# ou6_cs-base_V1_0.net
KiCad netlist of a schematic drawn in EAGLE
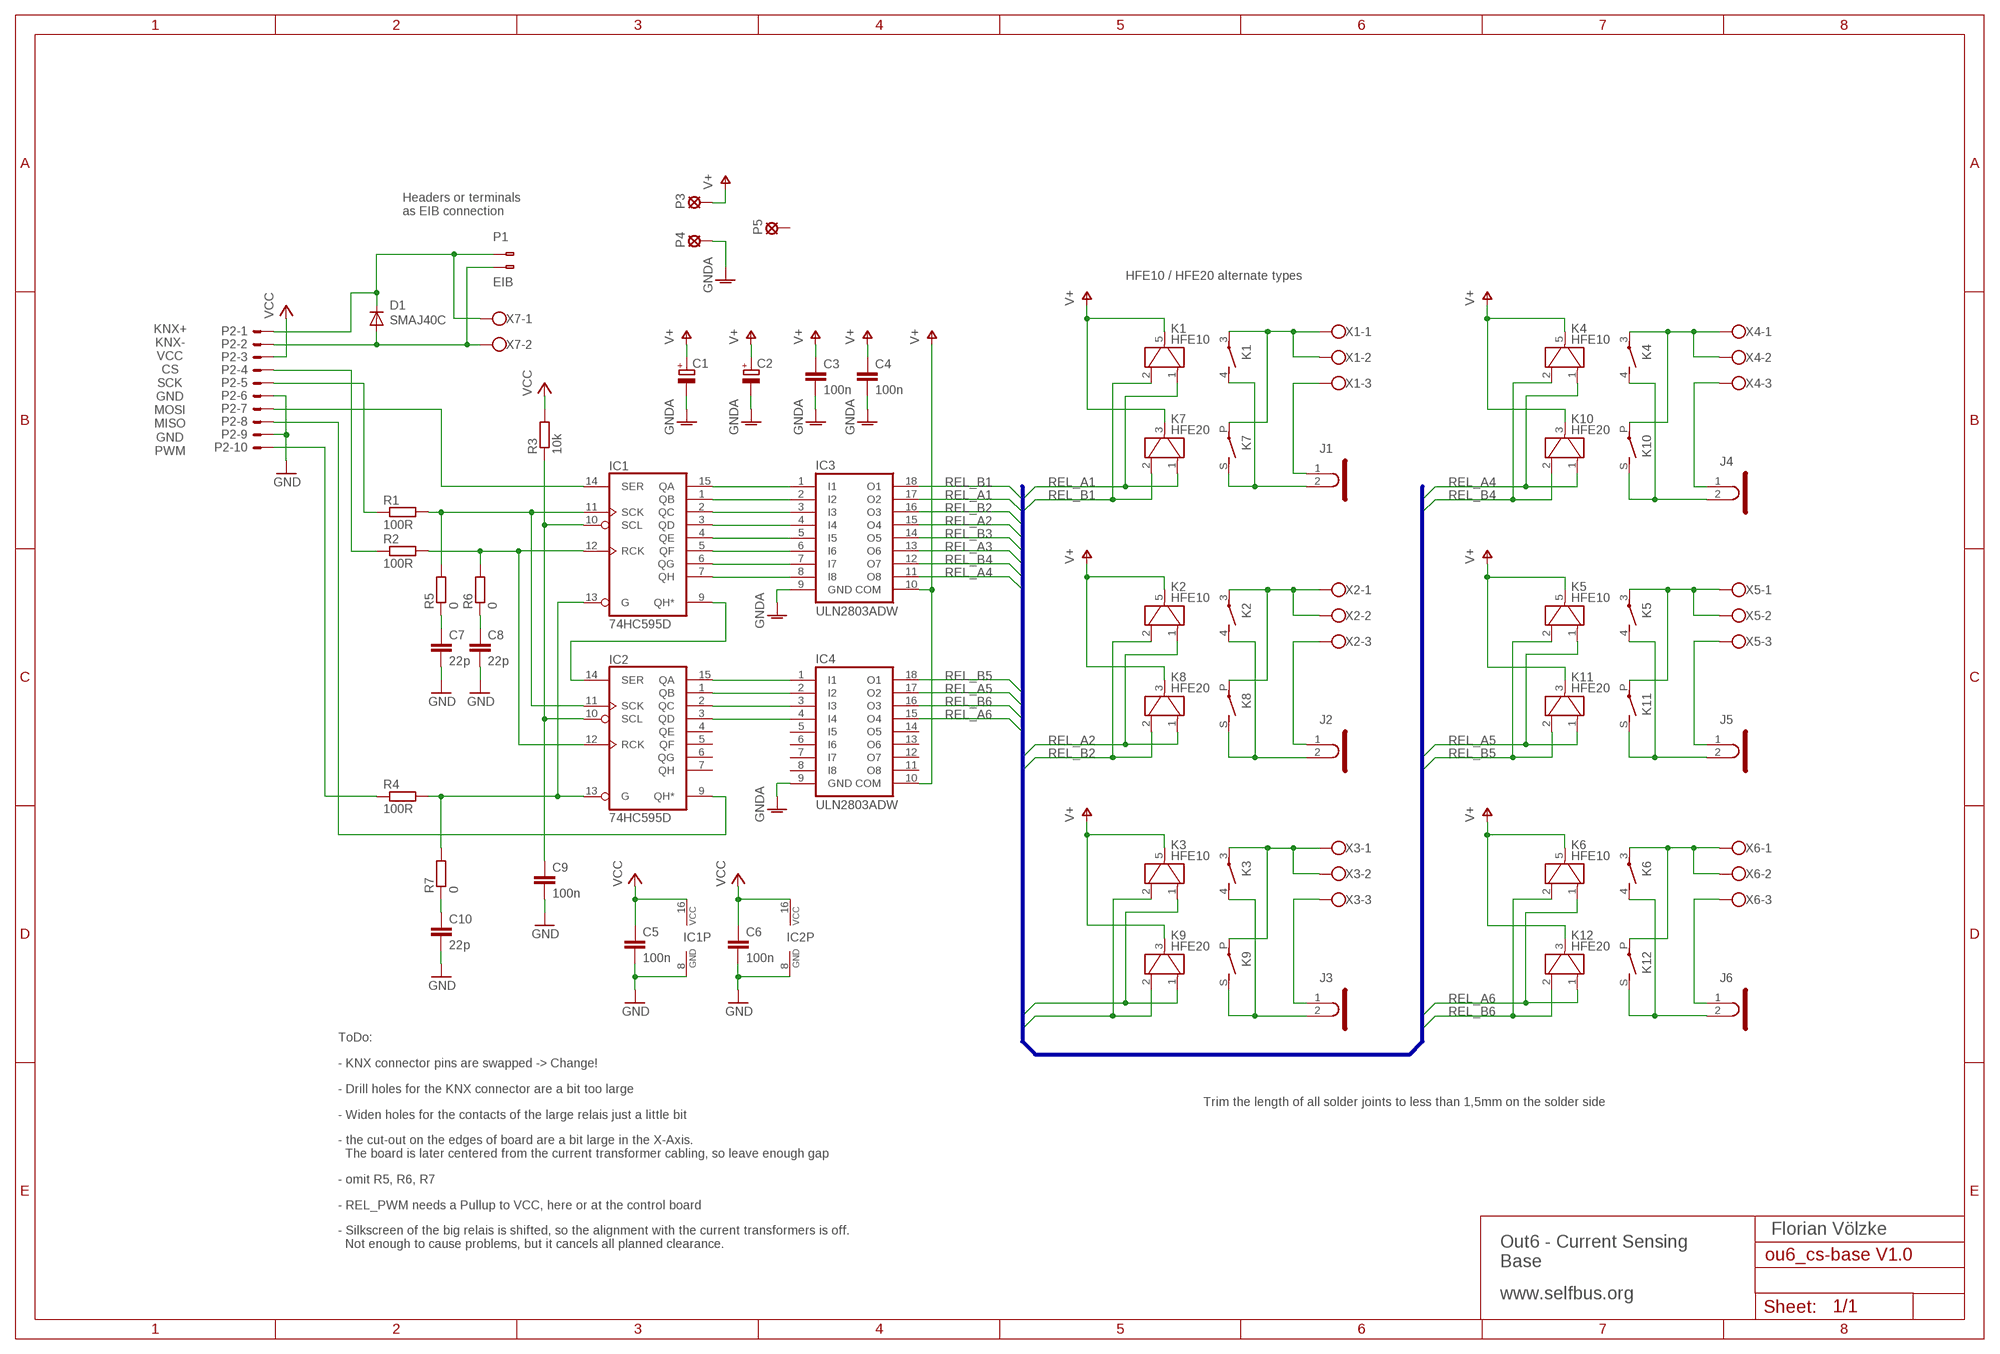
[diagram p0: schematic, sheet 1]

(export (version "E")
  (design (tool "Eeschema 10.0.6"))
  (components
    (comp (ref "C1")
      (value "CPOL-EUE5-13-20")
      (footprint "eagle-import:E5-13-20")
      (libsource (lib "eagle-import") (part "CPOL-EUE5-13-20"))
    )
    (comp (ref "C2")
      (value "CPOL-EUE5-13-20R")
      (footprint "eagle-import:E5-13-20R")
      (libsource (lib "eagle-import") (part "CPOL-EUE5-13-20R"))
    )
    (comp (ref "C3")
      (value "100n")
      (footprint "eagle-import:R0805M")
      (libsource (lib "eagle-import") (part "C-EUC0805M"))
    )
    (comp (ref "C4")
      (value "100n")
      (footprint "eagle-import:R0805M")
      (libsource (lib "eagle-import") (part "C-EUC0805M"))
    )
    (comp (ref "C5")
      (value "100n")
      (footprint "eagle-import:R0805M")
      (libsource (lib "eagle-import") (part "C-EUC0805M"))
    )
    (comp (ref "C6")
      (value "100n")
      (footprint "eagle-import:R0805M")
      (libsource (lib "eagle-import") (part "C-EUC0805M"))
    )
    (comp (ref "C7")
      (value "22p")
      (footprint "eagle-import:R0805M")
      (libsource (lib "eagle-import") (part "C-EUC0805M"))
    )
    (comp (ref "C8")
      (value "22p")
      (footprint "eagle-import:R0805M")
      (libsource (lib "eagle-import") (part "C-EUC0805M"))
    )
    (comp (ref "C9")
      (value "100n")
      (footprint "eagle-import:R0805M")
      (libsource (lib "eagle-import") (part "C-EUC0805M"))
    )
    (comp (ref "C10")
      (value "22p")
      (footprint "eagle-import:R0805M")
      (libsource (lib "eagle-import") (part "C-EUC0805M"))
    )
    (comp (ref "D1")
      (value "SMAJ40C")
      (footprint "eagle-import:SMB")
      (libsource (lib "eagle-import") (part "D-SMB"))
    )
    (comp (ref "IC1")
      (value "74HC595D")
      (footprint "eagle-import:SO16")
      (libsource (lib "eagle-import") (part "74595DHC"))
    )
    (comp (ref "IC2")
      (value "74HC595D")
      (footprint "eagle-import:SO16")
      (libsource (lib "eagle-import") (part "74595DHC"))
    )
    (comp (ref "IC3")
      (value "ULN2803ADW")
      (footprint "eagle-import:SO18W")
      (libsource (lib "eagle-import") (part "ULN2803ADW"))
    )
    (comp (ref "IC4")
      (value "ULN2803ADW")
      (footprint "eagle-import:SO18W")
      (libsource (lib "eagle-import") (part "ULN2803ADW"))
    )
    (comp (ref "J1")
      (value "IXFORMER_PRIMONLY")
      (footprint "eagle-import:IXFORMERANTIPART")
      (libsource (lib "eagle-import") (part "IXFORMER_PRIMONLY"))
    )
    (comp (ref "J2")
      (value "IXFORMER_PRIMONLY")
      (footprint "eagle-import:IXFORMERANTIPART")
      (libsource (lib "eagle-import") (part "IXFORMER_PRIMONLY"))
    )
    (comp (ref "J3")
      (value "IXFORMER_PRIMONLY")
      (footprint "eagle-import:IXFORMERANTIPART")
      (libsource (lib "eagle-import") (part "IXFORMER_PRIMONLY"))
    )
    (comp (ref "J4")
      (value "IXFORMER_PRIMONLY")
      (footprint "eagle-import:IXFORMERANTIPART")
      (libsource (lib "eagle-import") (part "IXFORMER_PRIMONLY"))
    )
    (comp (ref "J5")
      (value "IXFORMER_PRIMONLY")
      (footprint "eagle-import:IXFORMERANTIPART")
      (libsource (lib "eagle-import") (part "IXFORMER_PRIMONLY"))
    )
    (comp (ref "J6")
      (value "IXFORMER_PRIMONLY")
      (footprint "eagle-import:IXFORMERANTIPART")
      (libsource (lib "eagle-import") (part "IXFORMER_PRIMONLY"))
    )
    (comp (ref "K1")
      (value "HFE10")
      (footprint "eagle-import:PCB_REL_BIG_POWER_NO")
      (libsource (lib "eagle-import") (part "BISTABLE2C_PCB_SNGLPINHFE10"))
    )
    (comp (ref "K2")
      (value "HFE10")
      (footprint "eagle-import:PCB_REL_BIG_POWER_NO")
      (libsource (lib "eagle-import") (part "BISTABLE2C_PCB_SNGLPINHFE10"))
    )
    (comp (ref "K3")
      (value "HFE10")
      (footprint "eagle-import:PCB_REL_BIG_POWER_NO")
      (libsource (lib "eagle-import") (part "BISTABLE2C_PCB_SNGLPINHFE10"))
    )
    (comp (ref "K4")
      (value "HFE10")
      (footprint "eagle-import:PCB_REL_BIG_POWER_NO")
      (libsource (lib "eagle-import") (part "BISTABLE2C_PCB_SNGLPINHFE10"))
    )
    (comp (ref "K5")
      (value "HFE10")
      (footprint "eagle-import:PCB_REL_BIG_POWER_NO")
      (libsource (lib "eagle-import") (part "BISTABLE2C_PCB_SNGLPINHFE10"))
    )
    (comp (ref "K6")
      (value "HFE10")
      (footprint "eagle-import:PCB_REL_BIG_POWER_NO")
      (libsource (lib "eagle-import") (part "BISTABLE2C_PCB_SNGLPINHFE10"))
    )
    (comp (ref "K7")
      (value "HFE20")
      (footprint "eagle-import:PCB_REL_HP_NO_SNGLPIN")
      (libsource (lib "eagle-import") (part "BISTABLE2C_PCB_SNGLPINHFE20"))
    )
    (comp (ref "K8")
      (value "HFE20")
      (footprint "eagle-import:PCB_REL_HP_NO_SNGLPIN")
      (libsource (lib "eagle-import") (part "BISTABLE2C_PCB_SNGLPINHFE20"))
    )
    (comp (ref "K9")
      (value "HFE20")
      (footprint "eagle-import:PCB_REL_HP_NO_SNGLPIN")
      (libsource (lib "eagle-import") (part "BISTABLE2C_PCB_SNGLPINHFE20"))
    )
    (comp (ref "K10")
      (value "HFE20")
      (footprint "eagle-import:PCB_REL_HP_NO_SNGLPIN")
      (libsource (lib "eagle-import") (part "BISTABLE2C_PCB_SNGLPINHFE20"))
    )
    (comp (ref "K11")
      (value "HFE20")
      (footprint "eagle-import:PCB_REL_HP_NO_SNGLPIN")
      (libsource (lib "eagle-import") (part "BISTABLE2C_PCB_SNGLPINHFE20"))
    )
    (comp (ref "K12")
      (value "HFE20")
      (footprint "eagle-import:PCB_REL_HP_NO_SNGLPIN")
      (libsource (lib "eagle-import") (part "BISTABLE2C_PCB_SNGLPINHFE20"))
    )
    (comp (ref "P1")
      (value "EIB")
      (footprint "eagle-import:BUSKLEMME243-724")
      (libsource (lib "eagle-import") (part "EIB"))
    )
    (comp (ref "P2")
      (value "ML10E")
      (footprint "eagle-import:ML10")
      (libsource (lib "eagle-import") (part "ML10?E"))
    )
    (comp (ref "P3")
      (value "SE1.5")
      (footprint "eagle-import:SE15")
      (libsource (lib "eagle-import") (part "SE1.5"))
    )
    (comp (ref "P4")
      (value "SE1.5")
      (footprint "eagle-import:SE15")
      (libsource (lib "eagle-import") (part "SE1.5"))
    )
    (comp (ref "P5")
      (value "SE1.5")
      (footprint "eagle-import:SE15")
      (libsource (lib "eagle-import") (part "SE1.5"))
    )
    (comp (ref "R1")
      (value "100R")
      (footprint "eagle-import:R0805M")
      (libsource (lib "eagle-import") (part "R-EU_R0805M"))
    )
    (comp (ref "R2")
      (value "100R")
      (footprint "eagle-import:R0805M")
      (libsource (lib "eagle-import") (part "R-EU_R0805M"))
    )
    (comp (ref "R3")
      (value "10k")
      (footprint "eagle-import:R0805M")
      (libsource (lib "eagle-import") (part "R-EU_R0805M"))
    )
    (comp (ref "R4")
      (value "100R")
      (footprint "eagle-import:R0805M")
      (libsource (lib "eagle-import") (part "R-EU_R0805M"))
    )
    (comp (ref "R5")
      (value "0")
      (footprint "eagle-import:R0805M")
      (libsource (lib "eagle-import") (part "R-EU_R0805M"))
    )
    (comp (ref "R6")
      (value "0")
      (footprint "eagle-import:R0805M")
      (libsource (lib "eagle-import") (part "R-EU_R0805M"))
    )
    (comp (ref "R7")
      (value "0")
      (footprint "eagle-import:R0805M")
      (libsource (lib "eagle-import") (part "R-EU_R0805M"))
    )
    (comp (ref "X1")
      (value "KLEMME3POL5_08")
      (footprint "eagle-import:KLEMME3POL5_08")
      (libsource (lib "eagle-import") (part "KLEMME3POL5_08"))
    )
    (comp (ref "X2")
      (value "KLEMME3POL5_08")
      (footprint "eagle-import:KLEMME3POL5_08")
      (libsource (lib "eagle-import") (part "KLEMME3POL5_08"))
    )
    (comp (ref "X3")
      (value "KLEMME3POL5_08")
      (footprint "eagle-import:KLEMME3POL5_08")
      (libsource (lib "eagle-import") (part "KLEMME3POL5_08"))
    )
    (comp (ref "X4")
      (value "KLEMME3POL5_08")
      (footprint "eagle-import:KLEMME3POL5_08")
      (libsource (lib "eagle-import") (part "KLEMME3POL5_08"))
    )
    (comp (ref "X5")
      (value "KLEMME3POL5_08")
      (footprint "eagle-import:KLEMME3POL5_08")
      (libsource (lib "eagle-import") (part "KLEMME3POL5_08"))
    )
    (comp (ref "X6")
      (value "KLEMME3POL5_08")
      (footprint "eagle-import:KLEMME3POL5_08")
      (libsource (lib "eagle-import") (part "KLEMME3POL5_08"))
    )
    (comp (ref "X7")
      (value "KLEMME2POL5_08")
      (footprint "eagle-import:KLEMME2POL5_08")
      (libsource (lib "eagle-import") (part "KLEMME2POL5_08"))
    )
  )
  (nets
    (net (code "1") (name "/REL_A1") (class "Default")
      (node (ref "IC3") (pin "17") (pinfunction "O2_17") (pintype "open_collector"))
      (node (ref "K1") (pin "1") (pinfunction "3_1") (pintype "passive"))
      (node (ref "K7") (pin "1") (pinfunction "3_1") (pintype "passive"))
    )
    (net (code "2") (name "/REL_A2") (class "Default")
      (node (ref "IC3") (pin "15") (pinfunction "O4_15") (pintype "open_collector"))
      (node (ref "K2") (pin "1") (pinfunction "3_1") (pintype "passive"))
      (node (ref "K8") (pin "1") (pinfunction "3_1") (pintype "passive"))
    )
    (net (code "3") (name "/REL_A3") (class "Default")
      (node (ref "IC3") (pin "13") (pinfunction "O6_13") (pintype "open_collector"))
      (node (ref "K3") (pin "1") (pinfunction "3_1") (pintype "passive"))
      (node (ref "K9") (pin "1") (pinfunction "3_1") (pintype "passive"))
    )
    (net (code "4") (name "/REL_A4") (class "Default")
      (node (ref "IC3") (pin "11") (pinfunction "O8_11") (pintype "open_collector"))
      (node (ref "K10") (pin "1") (pinfunction "3_1") (pintype "passive"))
      (node (ref "K4") (pin "1") (pinfunction "3_1") (pintype "passive"))
    )
    (net (code "5") (name "/REL_A5") (class "Default")
      (node (ref "IC4") (pin "17") (pinfunction "O2_17") (pintype "open_collector"))
      (node (ref "K11") (pin "1") (pinfunction "3_1") (pintype "passive"))
      (node (ref "K5") (pin "1") (pinfunction "3_1") (pintype "passive"))
    )
    (net (code "6") (name "/REL_A6") (class "Default")
      (node (ref "IC4") (pin "15") (pinfunction "O4_15") (pintype "open_collector"))
      (node (ref "K12") (pin "1") (pinfunction "3_1") (pintype "passive"))
      (node (ref "K6") (pin "1") (pinfunction "3_1") (pintype "passive"))
    )
    (net (code "7") (name "/REL_B1") (class "Default")
      (node (ref "IC3") (pin "18") (pinfunction "O1_18") (pintype "open_collector"))
      (node (ref "K1") (pin "2") (pinfunction "2_2") (pintype "passive"))
      (node (ref "K7") (pin "2") (pinfunction "2_2") (pintype "passive"))
    )
    (net (code "8") (name "/REL_B2") (class "Default")
      (node (ref "IC3") (pin "16") (pinfunction "O3_16") (pintype "open_collector"))
      (node (ref "K2") (pin "2") (pinfunction "2_2") (pintype "passive"))
      (node (ref "K8") (pin "2") (pinfunction "2_2") (pintype "passive"))
    )
    (net (code "9") (name "/REL_B3") (class "Default")
      (node (ref "IC3") (pin "14") (pinfunction "O5_14") (pintype "open_collector"))
      (node (ref "K3") (pin "2") (pinfunction "2_2") (pintype "passive"))
      (node (ref "K9") (pin "2") (pinfunction "2_2") (pintype "passive"))
    )
    (net (code "10") (name "/REL_B4") (class "Default")
      (node (ref "IC3") (pin "12") (pinfunction "O7_12") (pintype "open_collector"))
      (node (ref "K10") (pin "2") (pinfunction "2_2") (pintype "passive"))
      (node (ref "K4") (pin "2") (pinfunction "2_2") (pintype "passive"))
    )
    (net (code "11") (name "/REL_B5") (class "Default")
      (node (ref "IC4") (pin "18") (pinfunction "O1_18") (pintype "open_collector"))
      (node (ref "K11") (pin "2") (pinfunction "2_2") (pintype "passive"))
      (node (ref "K5") (pin "2") (pinfunction "2_2") (pintype "passive"))
    )
    (net (code "12") (name "/REL_B6") (class "Default")
      (node (ref "IC4") (pin "16") (pinfunction "O3_16") (pintype "open_collector"))
      (node (ref "K12") (pin "2") (pinfunction "2_2") (pintype "passive"))
      (node (ref "K6") (pin "2") (pinfunction "2_2") (pintype "passive"))
    )
    (net (code "13") (name "GND") (class "Default")
      (node (ref "C10") (pin "2") (pinfunction "2_2") (pintype "passive"))
      (node (ref "C5") (pin "2") (pinfunction "2_2") (pintype "passive"))
      (node (ref "C6") (pin "2") (pinfunction "2_2") (pintype "passive"))
      (node (ref "C7") (pin "2") (pinfunction "2_2") (pintype "passive"))
      (node (ref "C8") (pin "2") (pinfunction "2_2") (pintype "passive"))
      (node (ref "C9") (pin "2") (pinfunction "2_2") (pintype "passive"))
      (node (ref "IC1") (pin "8") (pinfunction "GND_8") (pintype "power_in"))
      (node (ref "IC2") (pin "8") (pinfunction "GND_8") (pintype "power_in"))
      (node (ref "P2") (pin "6") (pinfunction "S_6") (pintype "passive"))
      (node (ref "P2") (pin "9") (pinfunction "S_9") (pintype "passive"))
    )
    (net (code "14") (name "GNDA") (class "Default")
      (node (ref "C1") (pin "-") (pinfunction "-_-") (pintype "passive"))
      (node (ref "C2") (pin "-") (pinfunction "-_-") (pintype "passive"))
      (node (ref "C3") (pin "2") (pinfunction "2_2") (pintype "passive"))
      (node (ref "C4") (pin "2") (pinfunction "2_2") (pintype "passive"))
      (node (ref "IC3") (pin "9") (pinfunction "GND_9") (pintype "power_in"))
      (node (ref "IC4") (pin "9") (pinfunction "GND_9") (pintype "power_in"))
      (node (ref "P4") (pin "MP") (pinfunction "MP_MP") (pintype "passive"))
    )
    (net (code "15") (name "Net-(C7-Pad1)") (class "Default")
      (node (ref "C7") (pin "1") (pinfunction "1_1") (pintype "passive"))
      (node (ref "R5") (pin "1") (pinfunction "1_1") (pintype "passive"))
    )
    (net (code "16") (name "Net-(C8-Pad1)") (class "Default")
      (node (ref "C8") (pin "1") (pinfunction "1_1") (pintype "passive"))
      (node (ref "R6") (pin "1") (pinfunction "1_1") (pintype "passive"))
    )
    (net (code "17") (name "Net-(C10-Pad1)") (class "Default")
      (node (ref "C10") (pin "1") (pinfunction "1_1") (pintype "passive"))
      (node (ref "R7") (pin "1") (pinfunction "1_1") (pintype "passive"))
    )
    (net (code "18") (name "Net-(D1-A)") (class "Default")
      (node (ref "D1") (pin "2") (pinfunction "A_2") (pintype "passive"))
      (node (ref "P1") (pin "2") (pinfunction "B-2_2") (pintype "passive"))
      (node (ref "P2") (pin "2") (pinfunction "S_2") (pintype "passive"))
      (node (ref "X7") (pin "P$2") (pinfunction "KL_P$2") (pintype "passive"))
    )
    (net (code "19") (name "Net-(D1-C)") (class "Default")
      (node (ref "D1") (pin "1") (pinfunction "C_1") (pintype "passive"))
      (node (ref "P1") (pin "1") (pinfunction "B-1_1") (pintype "passive"))
      (node (ref "P2") (pin "1") (pinfunction "S_1") (pintype "passive"))
      (node (ref "X7") (pin "P$1") (pinfunction "KL_P$1") (pintype "passive"))
    )
    (net (code "20") (name "Net-(IC1A-G)") (class "Default")
      (node (ref "IC1") (pin "13") (pinfunction "G_13") (pintype "input"))
      (node (ref "IC2") (pin "13") (pinfunction "G_13") (pintype "input"))
      (node (ref "R4") (pin "2") (pinfunction "2_2") (pintype "passive"))
      (node (ref "R7") (pin "2") (pinfunction "2_2") (pintype "passive"))
    )
    (net (code "21") (name "Net-(IC1A-QA)") (class "Default")
      (node (ref "IC1") (pin "15") (pinfunction "QA_15") (pintype "tri_state"))
      (node (ref "IC3") (pin "1") (pinfunction "I1_1") (pintype "input"))
    )
    (net (code "22") (name "Net-(IC1A-QB)") (class "Default")
      (node (ref "IC1") (pin "1") (pinfunction "QB_1") (pintype "tri_state"))
      (node (ref "IC3") (pin "2") (pinfunction "I2_2") (pintype "input"))
    )
    (net (code "23") (name "Net-(IC1A-QC)") (class "Default")
      (node (ref "IC1") (pin "2") (pinfunction "QC_2") (pintype "tri_state"))
      (node (ref "IC3") (pin "3") (pinfunction "I3_3") (pintype "input"))
    )
    (net (code "24") (name "Net-(IC1A-QD)") (class "Default")
      (node (ref "IC1") (pin "3") (pinfunction "QD_3") (pintype "tri_state"))
      (node (ref "IC3") (pin "4") (pinfunction "I4_4") (pintype "input"))
    )
    (net (code "25") (name "Net-(IC1A-QE)") (class "Default")
      (node (ref "IC1") (pin "4") (pinfunction "QE_4") (pintype "tri_state"))
      (node (ref "IC3") (pin "5") (pinfunction "I5_5") (pintype "input"))
    )
    (net (code "26") (name "Net-(IC1A-QF)") (class "Default")
      (node (ref "IC1") (pin "5") (pinfunction "QF_5") (pintype "tri_state"))
      (node (ref "IC3") (pin "6") (pinfunction "I6_6") (pintype "input"))
    )
    (net (code "27") (name "Net-(IC1A-QG)") (class "Default")
      (node (ref "IC1") (pin "6") (pinfunction "QG_6") (pintype "tri_state"))
      (node (ref "IC3") (pin "7") (pinfunction "I7_7") (pintype "input"))
    )
    (net (code "28") (name "Net-(IC1A-QH)") (class "Default")
      (node (ref "IC1") (pin "7") (pinfunction "QH_7") (pintype "tri_state"))
      (node (ref "IC3") (pin "8") (pinfunction "I8_8") (pintype "input"))
    )
    (net (code "29") (name "Net-(IC1A-QH*)") (class "Default")
      (node (ref "IC1") (pin "9") (pinfunction "QH*_9") (pintype "tri_state"))
      (node (ref "IC2") (pin "14") (pinfunction "SER_14") (pintype "input"))
    )
    (net (code "30") (name "Net-(IC1A-RCK)") (class "Default")
      (node (ref "IC1") (pin "12") (pinfunction "RCK_12") (pintype "input"))
      (node (ref "IC2") (pin "12") (pinfunction "RCK_12") (pintype "input"))
      (node (ref "R2") (pin "2") (pinfunction "2_2") (pintype "passive"))
      (node (ref "R6") (pin "2") (pinfunction "2_2") (pintype "passive"))
    )
    (net (code "31") (name "Net-(IC1A-SCK)") (class "Default")
      (node (ref "IC1") (pin "11") (pinfunction "SCK_11") (pintype "input"))
      (node (ref "IC2") (pin "11") (pinfunction "SCK_11") (pintype "input"))
      (node (ref "R1") (pin "2") (pinfunction "2_2") (pintype "passive"))
      (node (ref "R5") (pin "2") (pinfunction "2_2") (pintype "passive"))
    )
    (net (code "32") (name "Net-(IC1A-SCL)") (class "Default")
      (node (ref "C9") (pin "1") (pinfunction "1_1") (pintype "passive"))
      (node (ref "IC1") (pin "10") (pinfunction "SCL_10") (pintype "input"))
      (node (ref "IC2") (pin "10") (pinfunction "SCL_10") (pintype "input"))
      (node (ref "R3") (pin "1") (pinfunction "1_1") (pintype "passive"))
    )
    (net (code "33") (name "Net-(IC1A-SER)") (class "Default")
      (node (ref "IC1") (pin "14") (pinfunction "SER_14") (pintype "input"))
      (node (ref "P2") (pin "7") (pinfunction "S_7") (pintype "passive"))
    )
    (net (code "34") (name "Net-(IC2A-QA)") (class "Default")
      (node (ref "IC2") (pin "15") (pinfunction "QA_15") (pintype "tri_state"))
      (node (ref "IC4") (pin "1") (pinfunction "I1_1") (pintype "input"))
    )
    (net (code "35") (name "Net-(IC2A-QB)") (class "Default")
      (node (ref "IC2") (pin "1") (pinfunction "QB_1") (pintype "tri_state"))
      (node (ref "IC4") (pin "2") (pinfunction "I2_2") (pintype "input"))
    )
    (net (code "36") (name "Net-(IC2A-QC)") (class "Default")
      (node (ref "IC2") (pin "2") (pinfunction "QC_2") (pintype "tri_state"))
      (node (ref "IC4") (pin "3") (pinfunction "I3_3") (pintype "input"))
    )
    (net (code "37") (name "Net-(IC2A-QD)") (class "Default")
      (node (ref "IC2") (pin "3") (pinfunction "QD_3") (pintype "tri_state"))
      (node (ref "IC4") (pin "4") (pinfunction "I4_4") (pintype "input"))
    )
    (net (code "38") (name "Net-(IC2A-QH*)") (class "Default")
      (node (ref "IC2") (pin "9") (pinfunction "QH*_9") (pintype "tri_state"))
      (node (ref "P2") (pin "8") (pinfunction "S_8") (pintype "passive"))
    )
    (net (code "39") (name "Net-(K1B-P)") (class "Default")
      (node (ref "K1") (pin "3") (pinfunction "P_3") (pintype "passive"))
      (node (ref "K7") (pin "P") (pinfunction "P_P") (pintype "passive"))
      (node (ref "X1") (pin "P$1") (pinfunction "KL_P$1") (pintype "passive"))
      (node (ref "X1") (pin "P$2") (pinfunction "KL_P$2") (pintype "passive"))
    )
    (net (code "40") (name "Net-(K1B-S)") (class "Default")
      (node (ref "J1") (pin "2") (pinfunction "2_2") (pintype "passive"))
      (node (ref "K1") (pin "4") (pinfunction "S_4") (pintype "passive"))
      (node (ref "K7") (pin "S") (pinfunction "S_S") (pintype "passive"))
    )
    (net (code "41") (name "Net-(K2B-P)") (class "Default")
      (node (ref "K2") (pin "3") (pinfunction "P_3") (pintype "passive"))
      (node (ref "K8") (pin "P") (pinfunction "P_P") (pintype "passive"))
      (node (ref "X2") (pin "P$1") (pinfunction "KL_P$1") (pintype "passive"))
      (node (ref "X2") (pin "P$2") (pinfunction "KL_P$2") (pintype "passive"))
    )
    (net (code "42") (name "Net-(K2B-S)") (class "Default")
      (node (ref "J2") (pin "2") (pinfunction "2_2") (pintype "passive"))
      (node (ref "K2") (pin "4") (pinfunction "S_4") (pintype "passive"))
      (node (ref "K8") (pin "S") (pinfunction "S_S") (pintype "passive"))
    )
    (net (code "43") (name "Net-(K3B-P)") (class "Default")
      (node (ref "K3") (pin "3") (pinfunction "P_3") (pintype "passive"))
      (node (ref "K9") (pin "P") (pinfunction "P_P") (pintype "passive"))
      (node (ref "X3") (pin "P$1") (pinfunction "KL_P$1") (pintype "passive"))
      (node (ref "X3") (pin "P$2") (pinfunction "KL_P$2") (pintype "passive"))
    )
    (net (code "44") (name "Net-(K3B-S)") (class "Default")
      (node (ref "J3") (pin "2") (pinfunction "2_2") (pintype "passive"))
      (node (ref "K3") (pin "4") (pinfunction "S_4") (pintype "passive"))
      (node (ref "K9") (pin "S") (pinfunction "S_S") (pintype "passive"))
    )
    (net (code "45") (name "Net-(K4B-P)") (class "Default")
      (node (ref "K10") (pin "P") (pinfunction "P_P") (pintype "passive"))
      (node (ref "K4") (pin "3") (pinfunction "P_3") (pintype "passive"))
      (node (ref "X4") (pin "P$1") (pinfunction "KL_P$1") (pintype "passive"))
      (node (ref "X4") (pin "P$2") (pinfunction "KL_P$2") (pintype "passive"))
    )
    (net (code "46") (name "Net-(K4B-S)") (class "Default")
      (node (ref "J4") (pin "2") (pinfunction "2_2") (pintype "passive"))
      (node (ref "K10") (pin "S") (pinfunction "S_S") (pintype "passive"))
      (node (ref "K4") (pin "4") (pinfunction "S_4") (pintype "passive"))
    )
    (net (code "47") (name "Net-(K5B-P)") (class "Default")
      (node (ref "K11") (pin "P") (pinfunction "P_P") (pintype "passive"))
      (node (ref "K5") (pin "3") (pinfunction "P_3") (pintype "passive"))
      (node (ref "X5") (pin "P$1") (pinfunction "KL_P$1") (pintype "passive"))
      (node (ref "X5") (pin "P$2") (pinfunction "KL_P$2") (pintype "passive"))
    )
    (net (code "48") (name "Net-(K5B-S)") (class "Default")
      (node (ref "J5") (pin "2") (pinfunction "2_2") (pintype "passive"))
      (node (ref "K11") (pin "S") (pinfunction "S_S") (pintype "passive"))
      (node (ref "K5") (pin "4") (pinfunction "S_4") (pintype "passive"))
    )
    (net (code "49") (name "Net-(K6B-P)") (class "Default")
      (node (ref "K12") (pin "P") (pinfunction "P_P") (pintype "passive"))
      (node (ref "K6") (pin "3") (pinfunction "P_3") (pintype "passive"))
      (node (ref "X6") (pin "P$1") (pinfunction "KL_P$1") (pintype "passive"))
      (node (ref "X6") (pin "P$2") (pinfunction "KL_P$2") (pintype "passive"))
    )
    (net (code "50") (name "Net-(K6B-S)") (class "Default")
      (node (ref "J6") (pin "2") (pinfunction "2_2") (pintype "passive"))
      (node (ref "K12") (pin "S") (pinfunction "S_S") (pintype "passive"))
      (node (ref "K6") (pin "4") (pinfunction "S_4") (pintype "passive"))
    )
    (net (code "51") (name "Net-(P2B-S)") (class "Default")
      (node (ref "P2") (pin "10") (pinfunction "S_10") (pintype "passive"))
      (node (ref "R4") (pin "1") (pinfunction "1_1") (pintype "passive"))
    )
    (net (code "52") (name "Net-(P2E-S)") (class "Default")
      (node (ref "P2") (pin "4") (pinfunction "S_4") (pintype "passive"))
      (node (ref "R2") (pin "1") (pinfunction "1_1") (pintype "passive"))
    )
    (net (code "53") (name "Net-(P2F-S)") (class "Default")
      (node (ref "P2") (pin "5") (pinfunction "S_5") (pintype "passive"))
      (node (ref "R1") (pin "1") (pinfunction "1_1") (pintype "passive"))
    )
    (net (code "54") (name "Net-(X1C-KL)") (class "Default")
      (node (ref "J1") (pin "1") (pinfunction "1_1") (pintype "passive"))
      (node (ref "X1") (pin "P$3") (pinfunction "KL_P$3") (pintype "passive"))
    )
    (net (code "55") (name "Net-(X2C-KL)") (class "Default")
      (node (ref "J2") (pin "1") (pinfunction "1_1") (pintype "passive"))
      (node (ref "X2") (pin "P$3") (pinfunction "KL_P$3") (pintype "passive"))
    )
    (net (code "56") (name "Net-(X3C-KL)") (class "Default")
      (node (ref "J3") (pin "1") (pinfunction "1_1") (pintype "passive"))
      (node (ref "X3") (pin "P$3") (pinfunction "KL_P$3") (pintype "passive"))
    )
    (net (code "57") (name "Net-(X4C-KL)") (class "Default")
      (node (ref "J4") (pin "1") (pinfunction "1_1") (pintype "passive"))
      (node (ref "X4") (pin "P$3") (pinfunction "KL_P$3") (pintype "passive"))
    )
    (net (code "58") (name "Net-(X5C-KL)") (class "Default")
      (node (ref "J5") (pin "1") (pinfunction "1_1") (pintype "passive"))
      (node (ref "X5") (pin "P$3") (pinfunction "KL_P$3") (pintype "passive"))
    )
    (net (code "59") (name "Net-(X6C-KL)") (class "Default")
      (node (ref "J6") (pin "1") (pinfunction "1_1") (pintype "passive"))
      (node (ref "X6") (pin "P$3") (pinfunction "KL_P$3") (pintype "passive"))
    )
    (net (code "60") (name "V+") (class "Default")
      (node (ref "C1") (pin "+") (pinfunction "+_+") (pintype "passive"))
      (node (ref "C2") (pin "+") (pinfunction "+_+") (pintype "passive"))
      (node (ref "C3") (pin "1") (pinfunction "1_1") (pintype "passive"))
      (node (ref "C4") (pin "1") (pinfunction "1_1") (pintype "passive"))
      (node (ref "IC3") (pin "10") (pinfunction "COM_10") (pintype "passive"))
      (node (ref "IC4") (pin "10") (pinfunction "COM_10") (pintype "passive"))
      (node (ref "K1") (pin "5") (pinfunction "1_5") (pintype "passive"))
      (node (ref "K10") (pin "3") (pinfunction "1_3") (pintype "passive"))
      (node (ref "K11") (pin "3") (pinfunction "1_3") (pintype "passive"))
      (node (ref "K12") (pin "3") (pinfunction "1_3") (pintype "passive"))
      (node (ref "K2") (pin "5") (pinfunction "1_5") (pintype "passive"))
      (node (ref "K3") (pin "5") (pinfunction "1_5") (pintype "passive"))
      (node (ref "K4") (pin "5") (pinfunction "1_5") (pintype "passive"))
      (node (ref "K5") (pin "5") (pinfunction "1_5") (pintype "passive"))
      (node (ref "K6") (pin "5") (pinfunction "1_5") (pintype "passive"))
      (node (ref "K7") (pin "3") (pinfunction "1_3") (pintype "passive"))
      (node (ref "K8") (pin "3") (pinfunction "1_3") (pintype "passive"))
      (node (ref "K9") (pin "3") (pinfunction "1_3") (pintype "passive"))
      (node (ref "P3") (pin "MP") (pinfunction "MP_MP") (pintype "passive"))
    )
    (net (code "61") (name "VCC") (class "Default")
      (node (ref "C5") (pin "1") (pinfunction "1_1") (pintype "passive"))
      (node (ref "C6") (pin "1") (pinfunction "1_1") (pintype "passive"))
      (node (ref "IC1") (pin "16") (pinfunction "VCC_16") (pintype "power_in"))
      (node (ref "IC2") (pin "16") (pinfunction "VCC_16") (pintype "power_in"))
      (node (ref "P2") (pin "3") (pinfunction "S_3") (pintype "passive"))
      (node (ref "R3") (pin "2") (pinfunction "2_2") (pintype "passive"))
    )
    (net (code "62") (name "unconnected-(IC2A-QE-Pad4)") (class "Default")
      (node (ref "IC2") (pin "4") (pinfunction "QE_4") (pintype "tri_state"))
    )
    (net (code "63") (name "unconnected-(IC2A-QF-Pad5)") (class "Default")
      (node (ref "IC2") (pin "5") (pinfunction "QF_5") (pintype "tri_state"))
    )
    (net (code "64") (name "unconnected-(IC2A-QG-Pad6)") (class "Default")
      (node (ref "IC2") (pin "6") (pinfunction "QG_6") (pintype "tri_state"))
    )
    (net (code "65") (name "unconnected-(IC2A-QH-Pad7)") (class "Default")
      (node (ref "IC2") (pin "7") (pinfunction "QH_7") (pintype "tri_state"))
    )
    (net (code "66") (name "unconnected-(IC4-I5-Pad5)") (class "Default")
      (node (ref "IC4") (pin "5") (pinfunction "I5_5") (pintype "input"))
    )
    (net (code "67") (name "unconnected-(IC4-I6-Pad6)") (class "Default")
      (node (ref "IC4") (pin "6") (pinfunction "I6_6") (pintype "input"))
    )
    (net (code "68") (name "unconnected-(IC4-I7-Pad7)") (class "Default")
      (node (ref "IC4") (pin "7") (pinfunction "I7_7") (pintype "input"))
    )
    (net (code "69") (name "unconnected-(IC4-I8-Pad8)") (class "Default")
      (node (ref "IC4") (pin "8") (pinfunction "I8_8") (pintype "input"))
    )
    (net (code "70") (name "unconnected-(IC4-O5-Pad14)") (class "Default")
      (node (ref "IC4") (pin "14") (pinfunction "O5_14") (pintype "open_collector"))
    )
    (net (code "71") (name "unconnected-(IC4-O6-Pad13)") (class "Default")
      (node (ref "IC4") (pin "13") (pinfunction "O6_13") (pintype "open_collector"))
    )
    (net (code "72") (name "unconnected-(IC4-O7-Pad12)") (class "Default")
      (node (ref "IC4") (pin "12") (pinfunction "O7_12") (pintype "open_collector"))
    )
    (net (code "73") (name "unconnected-(IC4-O8-Pad11)") (class "Default")
      (node (ref "IC4") (pin "11") (pinfunction "O8_11") (pintype "open_collector"))
    )
    (net (code "74") (name "unconnected-(P5-PadMP)") (class "Default")
      (node (ref "P5") (pin "MP") (pinfunction "MP_MP") (pintype "passive"))
    )
  )
)
